# contactor_control.net
KiCad netlist of a schematic drawn in Altium Designer
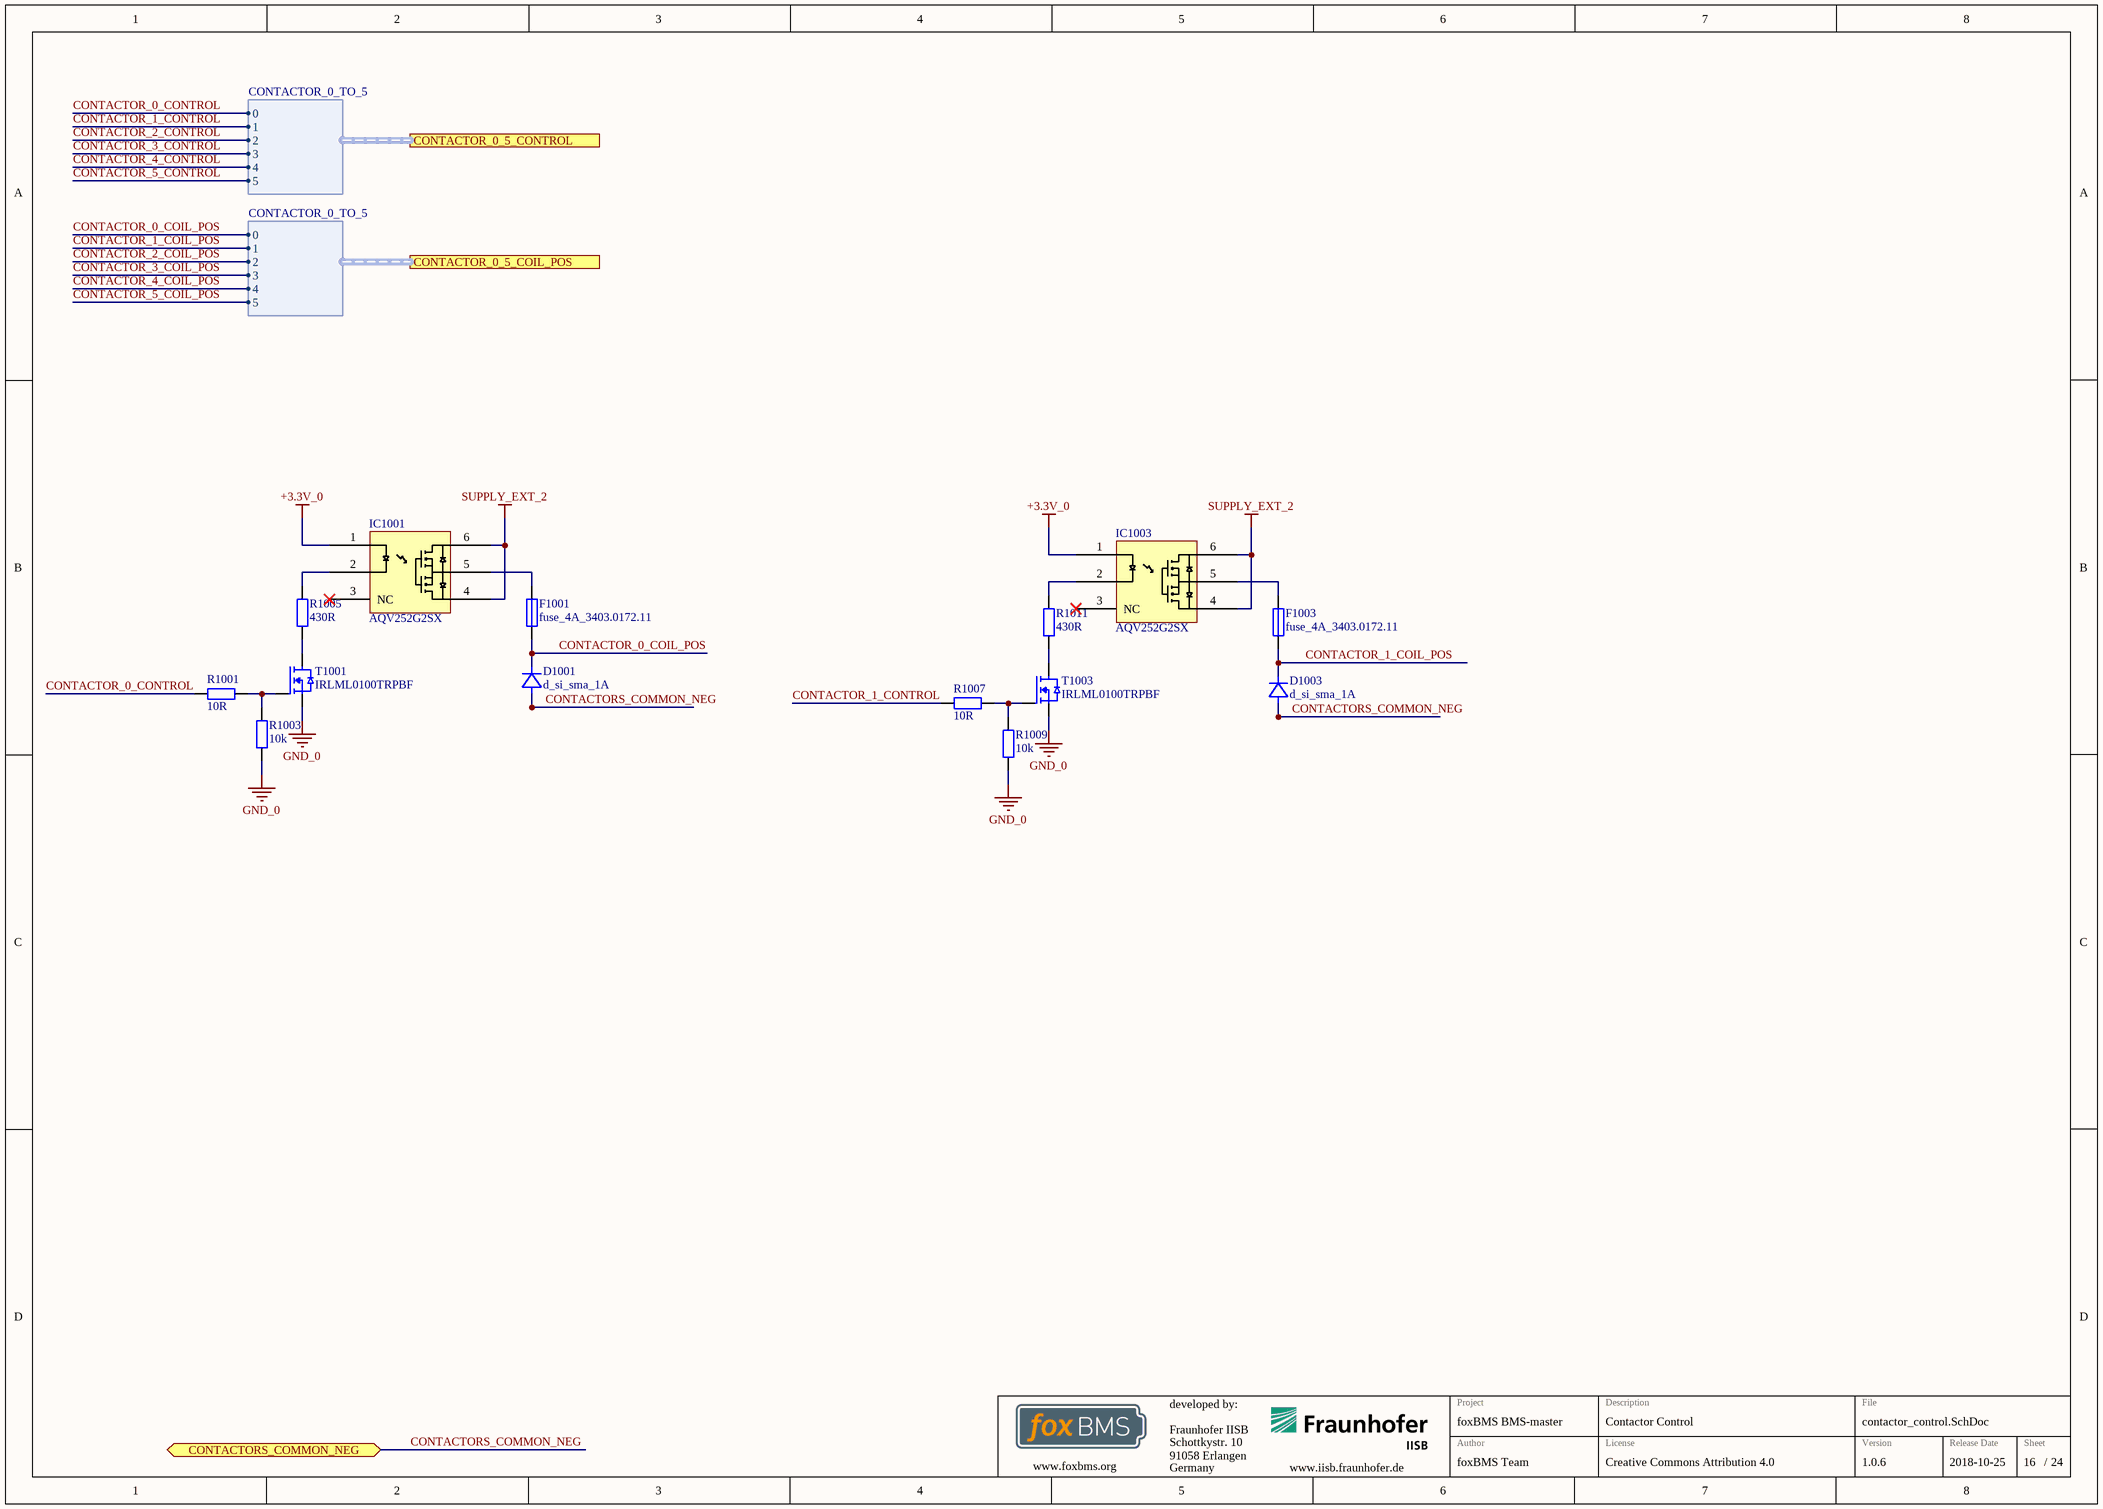
[diagram p0: contactor_control.SchDoc]

(export (version "E")
  (design (tool "Eeschema 10.0.6"))
  (components
    (comp (ref "D1001")
      (value "d_si_sma_1A")
      (footprint "DIOM4326X24N")
      (description "Standard Recovery Diode, 100 V, 1 A, Single, 1 V, 2 µs, 30 A")
      (fields (field (name "MANUFACTURER") "ON Semiconductor"))
      (libsource (lib "OE750") (part "D"))
    )
    (comp (ref "D1003")
      (value "d_si_sma_1A")
      (footprint "DIOM4326X24N")
      (description "Standard Recovery Diode, 100 V, 1 A, Single, 1 V, 2 µs, 30 A")
      (fields (field (name "MANUFACTURER") "ON Semiconductor"))
      (libsource (lib "OE750") (part "D"))
    )
    (comp (ref "F1001")
      (value "fuse_4A_3403.0172.11")
      (footprint "Schurter_UMT_250")
      (description "Schurter SMD Fuse 4.0A UMT 3403.0172.11")
      (fields (field (name "MANUFACTURER") "Schurter"))
      (libsource (lib "OE750") (part "R_Fuse"))
    )
    (comp (ref "F1003")
      (value "fuse_4A_3403.0172.11")
      (footprint "Schurter_UMT_250")
      (description "Schurter SMD Fuse 4.0A UMT 3403.0172.11")
      (fields (field (name "MANUFACTURER") "Schurter"))
      (libsource (lib "OE750") (part "R_Fuse"))
    )
    (comp (ref "IC1001")
      (value "AQV252G2SX")
      (footprint "SOP254P680X220-6N")
      (description "PhotoMOS Relay")
      (fields (field (name "MANUFACTURER") "Panasonic"))
      (libsource (lib "OE750") (part "AQV252G2SX"))
    )
    (comp (ref "IC1003")
      (value "AQV252G2SX")
      (footprint "SOP254P680X220-6N")
      (description "PhotoMOS Relay")
      (fields (field (name "MANUFACTURER") "Panasonic"))
      (libsource (lib "OE750") (part "AQV252G2SX"))
    )
    (comp (ref "R1001")
      (value "10R")
      (footprint "RESC1608X05N")
      (description "SMD Resistor 10R 0603")
      (fields (field (name "PART NUMBER") "gen_R_10R_0603") (field (name "TOLERANCE") "1%"))
      (libsource (lib "OE750") (part "R"))
    )
    (comp (ref "R1003")
      (value "10k")
      (footprint "RESC1608X05N")
      (description "SMD Resistor 10k 0603")
      (fields (field (name "PART NUMBER") "gen_R_10k_0603") (field (name "TOLERANCE") "1%"))
      (libsource (lib "OE750") (part "R"))
    )
    (comp (ref "R1005")
      (value "430R")
      (footprint "RESC1608X05N")
      (description "SMD Resistor 430R 0603")
      (fields (field (name "PART NUMBER") "gen_R_430R_0603") (field (name "TOLERANCE") "1%"))
      (libsource (lib "OE750") (part "R"))
    )
    (comp (ref "R1007")
      (value "10R")
      (footprint "RESC1608X05N")
      (description "SMD Resistor 10R 0603")
      (fields (field (name "PART NUMBER") "gen_R_10R_0603") (field (name "TOLERANCE") "1%"))
      (libsource (lib "OE750") (part "R"))
    )
    (comp (ref "R1009")
      (value "10k")
      (footprint "RESC1608X05N")
      (description "SMD Resistor 10k 0603")
      (fields (field (name "PART NUMBER") "gen_R_10k_0603") (field (name "TOLERANCE") "1%"))
      (libsource (lib "OE750") (part "R"))
    )
    (comp (ref "R1011")
      (value "430R")
      (footprint "RESC1608X05N")
      (description "SMD Resistor 430R 0603")
      (fields (field (name "PART NUMBER") "gen_R_430R_0603") (field (name "TOLERANCE") "1%"))
      (libsource (lib "OE750") (part "R"))
    )
    (comp (ref "T1001")
      (value "IRLML0100TRPBF")
      (footprint "SOT95P237X110-3N")
      (description "MOSFET-Transistor, n-Kanal, 1.6 A, 100 V, 0.178 ohm, 10 V, 2.5 V")
      (fields (field (name "MANUFACTURER") "Infineon"))
      (libsource (lib "OE750") (part "NMOS"))
    )
    (comp (ref "T1003")
      (value "IRLML0100TRPBF")
      (footprint "SOT95P237X110-3N")
      (description "MOSFET-Transistor, n-Kanal, 1.6 A, 100 V, 0.178 ohm, 10 V, 2.5 V")
      (fields (field (name "MANUFACTURER") "Infineon"))
      (libsource (lib "OE750") (part "NMOS"))
    )
  )
  (nets
    (net (code "2") (name "+3.3V_0") (class "Default")
      (node (ref "IC1001") (pin "1") (pintype "passive"))
      (node (ref "IC1003") (pin "1") (pintype "passive"))
    )
    (net (code "3") (name "/CONTACTORS_COMMON_NEG") (class "Default")
      (node (ref "D1001") (pin "2") (pinfunction "A_2") (pintype "passive"))
      (node (ref "D1003") (pin "2") (pinfunction "A_2") (pintype "passive"))
    )
    (net (code "4") (name "/CONTACTOR_0_COIL_POS") (class "Default")
      (node (ref "D1001") (pin "1") (pinfunction "K_1") (pintype "passive"))
      (node (ref "F1001") (pin "2") (pinfunction "2_2") (pintype "passive"))
    )
    (net (code "5") (name "/CONTACTOR_0_CONTROL") (class "Default")
      (node (ref "R1001") (pin "2") (pinfunction "2_2") (pintype "passive"))
    )
    (net (code "6") (name "/CONTACTOR_1_COIL_POS") (class "Default")
      (node (ref "D1003") (pin "1") (pinfunction "K_1") (pintype "passive"))
      (node (ref "F1003") (pin "2") (pinfunction "2_2") (pintype "passive"))
    )
    (net (code "7") (name "/CONTACTOR_1_CONTROL") (class "Default")
      (node (ref "R1007") (pin "2") (pinfunction "2_2") (pintype "passive"))
    )
    (net (code "17") (name "GND_0") (class "Default")
      (node (ref "R1003") (pin "1") (pinfunction "1_1") (pintype "passive"))
      (node (ref "R1009") (pin "1") (pinfunction "1_1") (pintype "passive"))
      (node (ref "T1001") (pin "S") (pinfunction "S_S") (pintype "passive"))
      (node (ref "T1003") (pin "S") (pinfunction "S_S") (pintype "passive"))
    )
    (net (code "18") (name "Net-(F1001-Pad1)") (class "Default")
      (node (ref "F1001") (pin "1") (pinfunction "1_1") (pintype "passive"))
      (node (ref "IC1001") (pin "5") (pintype "passive"))
    )
    (net (code "19") (name "Net-(F1003-Pad1)") (class "Default")
      (node (ref "F1003") (pin "1") (pinfunction "1_1") (pintype "passive"))
      (node (ref "IC1003") (pin "5") (pintype "passive"))
    )
    (net (code "20") (name "Net-(IC1001-Pad2)") (class "Default")
      (node (ref "IC1001") (pin "2") (pintype "power_in"))
      (node (ref "R1005") (pin "2") (pinfunction "2_2") (pintype "passive"))
    )
    (net (code "21") (name "Net-(IC1003-Pad2)") (class "Default")
      (node (ref "IC1003") (pin "2") (pintype "power_in"))
      (node (ref "R1011") (pin "2") (pinfunction "2_2") (pintype "passive"))
    )
    (net (code "22") (name "Net-(R1001-Pad1)") (class "Default")
      (node (ref "R1001") (pin "1") (pinfunction "1_1") (pintype "passive"))
      (node (ref "R1003") (pin "2") (pinfunction "2_2") (pintype "passive"))
      (node (ref "T1001") (pin "G") (pinfunction "G_G") (pintype "passive"))
    )
    (net (code "23") (name "Net-(R1005-Pad1)") (class "Default")
      (node (ref "R1005") (pin "1") (pinfunction "1_1") (pintype "passive"))
      (node (ref "T1001") (pin "D") (pinfunction "D_D") (pintype "passive"))
    )
    (net (code "24") (name "Net-(R1007-Pad1)") (class "Default")
      (node (ref "R1007") (pin "1") (pinfunction "1_1") (pintype "passive"))
      (node (ref "R1009") (pin "2") (pinfunction "2_2") (pintype "passive"))
      (node (ref "T1003") (pin "G") (pinfunction "G_G") (pintype "passive"))
    )
    (net (code "25") (name "Net-(R1011-Pad1)") (class "Default")
      (node (ref "R1011") (pin "1") (pinfunction "1_1") (pintype "passive"))
      (node (ref "T1003") (pin "D") (pinfunction "D_D") (pintype "passive"))
    )
    (net (code "26") (name "SUPPLY_EXT_2") (class "Default")
      (node (ref "IC1001") (pin "4") (pintype "passive"))
      (node (ref "IC1001") (pin "6") (pintype "passive"))
      (node (ref "IC1003") (pin "4") (pintype "passive"))
      (node (ref "IC1003") (pin "6") (pintype "passive"))
    )
    (net (code "27") (name "unconnected-(IC1001-NC-Pad3)") (class "Default")
      (node (ref "IC1001") (pin "3") (pinfunction "NC_3") (pintype "passive+no_connect"))
    )
    (net (code "28") (name "unconnected-(IC1003-NC-Pad3)") (class "Default")
      (node (ref "IC1003") (pin "3") (pinfunction "NC_3") (pintype "passive+no_connect"))
    )
  )
)
